# Power.net
KiCad netlist of a schematic drawn in Altium Designer
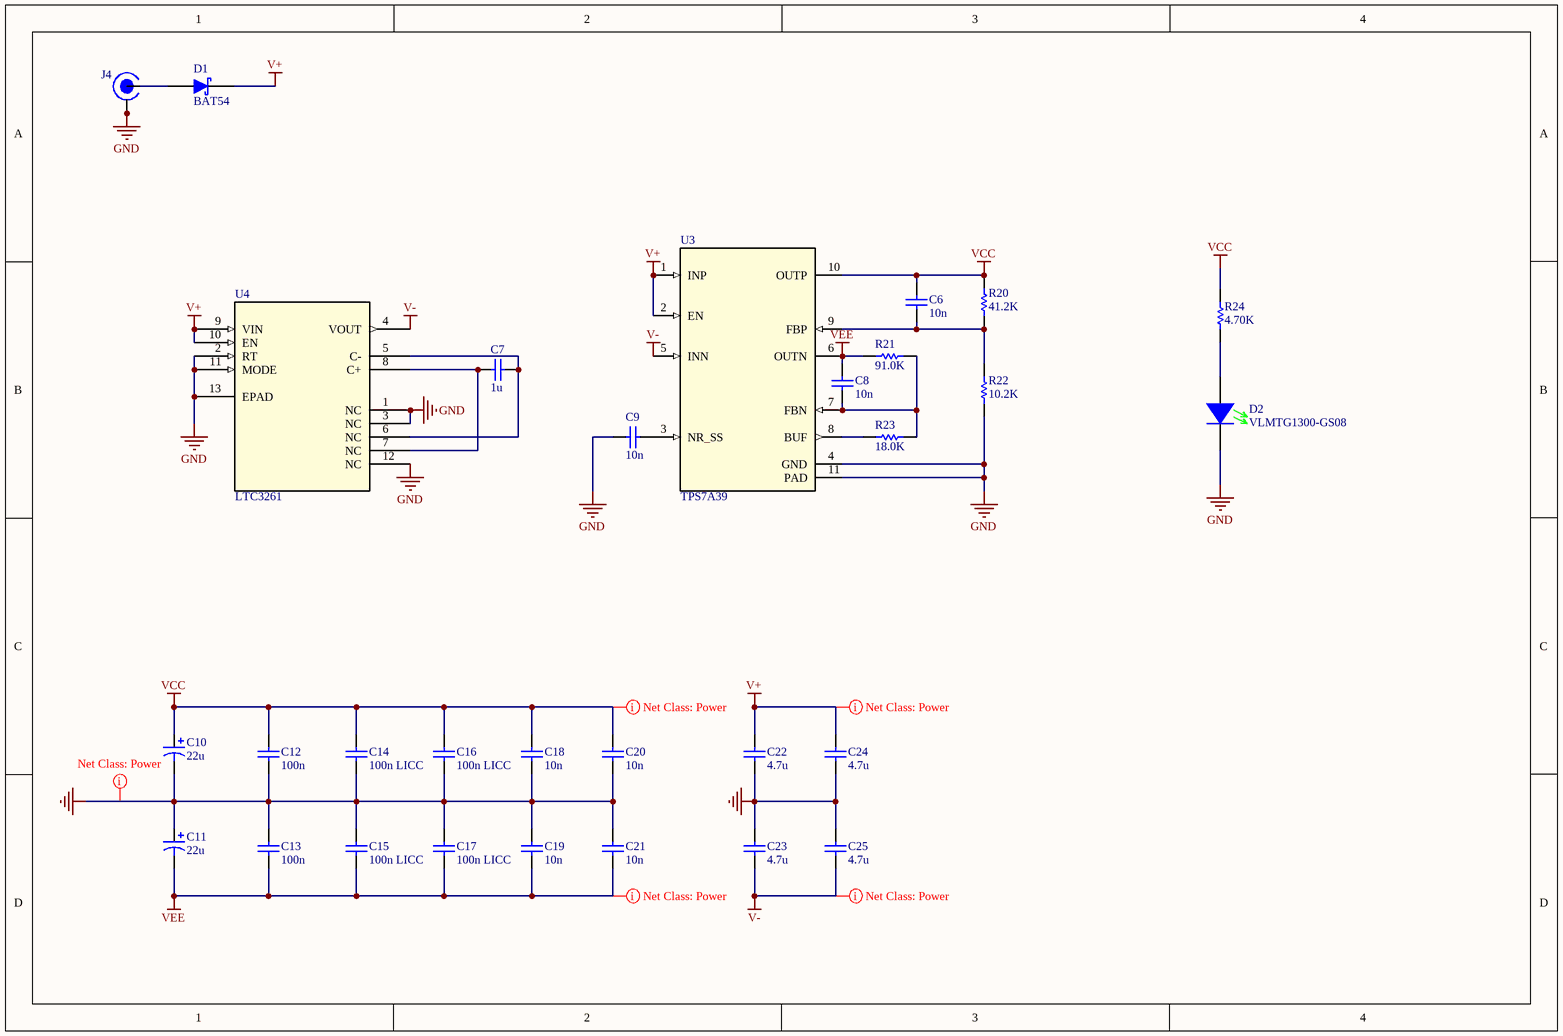
[diagram p0: Power.SchDoc]

(export (version "E")
  (design (tool "Eeschema 10.0.6"))
  (components
    (comp (ref "C6")
      (value "10n")
      (footprint "CAPC0402(1005)50_M")
      (description "CAP CER 10NF±5% 25V C0G 0402")
      (fields
        (field (name "MANUFACTURER") "Murata")
        (field (name "MANUFACTURER PART NUMBER") "GRM1555C1E103JE01D")
      )
      (libsource (lib "Murata GRM 0402") (part "Capacitor_Generic"))
    )
    (comp (ref "C7")
      (value "1u")
      (footprint "CAPC0805(2012)145_M")
      (description "Cap Ceramic 1uF 50V X7R 10% SMD 0805 125C Blister T/R")
      (fields
        (field (name "MANUFACTURER") "Yageo")
        (field (name "MANUFACTURER PART NUMBER") "CC0805KKX7R9BB105")
      )
      (libsource (lib "0805 Caps") (part "CC0805KKX7R9BB105"))
    )
    (comp (ref "C8")
      (value "10n")
      (footprint "CAPC0402(1005)50_M")
      (description "CAP CER 10NF±5% 25V C0G 0402")
      (fields
        (field (name "MANUFACTURER") "Murata")
        (field (name "MANUFACTURER PART NUMBER") "GRM1555C1E103JE01D")
      )
      (libsource (lib "Murata GRM 0402") (part "Capacitor_Generic"))
    )
    (comp (ref "C9")
      (value "10n")
      (footprint "CAPC0402(1005)50_M")
      (description "CAP CER 10NF±5% 25V C0G 0402")
      (fields
        (field (name "MANUFACTURER") "Murata")
        (field (name "MANUFACTURER PART NUMBER") "GRM1555C1E103JE01D")
      )
      (libsource (lib "Murata GRM 0402") (part "Capacitor_Generic"))
    )
    (comp (ref "C10")
      (value "22u")
      (footprint "KEMET B_M")
      (description "CAP TANT 22UF 10% 16V 1411")
      (fields
        (field (name "MANUFACTURER") "KEMET")
        (field (name "MANUFACTURER PART NUMBER") "T491B226K016AT")
      )
      (libsource (lib "Misc Caps") (part "T491B226K016AT"))
    )
    (comp (ref "C11")
      (value "22u")
      (footprint "KEMET B_M")
      (description "CAP TANT 22UF 10% 16V 1411")
      (fields
        (field (name "MANUFACTURER") "KEMET")
        (field (name "MANUFACTURER PART NUMBER") "T491B226K016AT")
      )
      (libsource (lib "Misc Caps") (part "T491B226K016AT"))
    )
    (comp (ref "C12")
      (value "100n")
      (footprint "CAPC0603(1608)100_M")
      (description "CAPACITOR CERAMIC, 0.1UF, 50V, X7R, 10%, 0603")
      (fields
        (field (name "MANUFACTURER") "Yageo")
        (field (name "MANUFACTURER PART NUMBER") "CC0603KRX7R9BB104")
      )
      (libsource (lib "0603 Caps") (part "CC0603KRX7R9BB104"))
    )
    (comp (ref "C13")
      (value "100n")
      (footprint "CAPC0603(1608)100_M")
      (description "CAPACITOR CERAMIC, 0.1UF, 50V, X7R, 10%, 0603")
      (fields
        (field (name "MANUFACTURER") "Yageo")
        (field (name "MANUFACTURER PART NUMBER") "CC0603KRX7R9BB104")
      )
      (libsource (lib "0603 Caps") (part "CC0603KRX7R9BB104"))
    )
    (comp (ref "C14")
      (value "100n LICC")
      (footprint "CAPC0306_M")
      (description "CAP CER 0.1UF 25V X7R 0306")
      (fields
        (field (name "MANUFACTURER") "Taiyo Yuden")
        (field (name "MANUFACTURER PART NUMBER") "TWK107B7104MVHT")
      )
      (libsource (lib "Misc Caps") (part "TWK107B7104MVHT"))
    )
    (comp (ref "C15")
      (value "100n LICC")
      (footprint "CAPC0306_M")
      (description "CAP CER 0.1UF 25V X7R 0306")
      (fields
        (field (name "MANUFACTURER") "Taiyo Yuden")
        (field (name "MANUFACTURER PART NUMBER") "TWK107B7104MVHT")
      )
      (libsource (lib "Misc Caps") (part "TWK107B7104MVHT"))
    )
    (comp (ref "C16")
      (value "100n LICC")
      (footprint "CAPC0306_M")
      (description "CAP CER 0.1UF 25V X7R 0306")
      (fields
        (field (name "MANUFACTURER") "Taiyo Yuden")
        (field (name "MANUFACTURER PART NUMBER") "TWK107B7104MVHT")
      )
      (libsource (lib "Misc Caps") (part "TWK107B7104MVHT"))
    )
    (comp (ref "C17")
      (value "100n LICC")
      (footprint "CAPC0306_M")
      (description "CAP CER 0.1UF 25V X7R 0306")
      (fields
        (field (name "MANUFACTURER") "Taiyo Yuden")
        (field (name "MANUFACTURER PART NUMBER") "TWK107B7104MVHT")
      )
      (libsource (lib "Misc Caps") (part "TWK107B7104MVHT"))
    )
    (comp (ref "C18")
      (value "10n")
      (footprint "CAPC0402(1005)50_M")
      (description "CAP CER 10NF±10% 50V X7R 0402")
      (fields (field (name "PART NUMBER") "GRM155R71H103KA88") (field (name "TOLERANCE") "±10%"))
      (libsource (lib "Murata GRM 0402") (part "Capacitor_Generic"))
    )
    (comp (ref "C19")
      (value "10n")
      (footprint "CAPC0402(1005)50_M")
      (description "CAP CER 10NF±10% 50V X7R 0402")
      (fields (field (name "PART NUMBER") "GRM155R71H103KA88") (field (name "TOLERANCE") "±10%"))
      (libsource (lib "Murata GRM 0402") (part "Capacitor_Generic"))
    )
    (comp (ref "C20")
      (value "10n")
      (footprint "CAPC0402(1005)50_M")
      (description "CAP CER 10NF±10% 50V X7R 0402")
      (fields (field (name "PART NUMBER") "GRM155R71H103KA88") (field (name "TOLERANCE") "±10%"))
      (libsource (lib "Murata GRM 0402") (part "Capacitor_Generic"))
    )
    (comp (ref "C21")
      (value "10n")
      (footprint "CAPC0402(1005)50_M")
      (description "CAP CER 10NF±10% 50V X7R 0402")
      (fields (field (name "PART NUMBER") "GRM155R71H103KA88") (field (name "TOLERANCE") "±10%"))
      (libsource (lib "Murata GRM 0402") (part "Capacitor_Generic"))
    )
    (comp (ref "C22")
      (value "4.7u")
      (footprint "CAPC0805(2012)100_M")
      (description "CAP CER 4.7UF 50V X7R 0805")
      (fields
        (field (name "MANUFACTURER") "Murata")
        (field (name "MANUFACTURER PART NUMBER") "GRM21BZ71H475KE15K")
      )
      (libsource (lib "0805 Caps") (part "GRM21BZ71H475KE15K"))
    )
    (comp (ref "C23")
      (value "4.7u")
      (footprint "CAPC0805(2012)100_M")
      (description "CAP CER 4.7UF 50V X7R 0805")
      (fields
        (field (name "MANUFACTURER") "Murata")
        (field (name "MANUFACTURER PART NUMBER") "GRM21BZ71H475KE15K")
      )
      (libsource (lib "0805 Caps") (part "GRM21BZ71H475KE15K"))
    )
    (comp (ref "C24")
      (value "4.7u")
      (footprint "CAPC0805(2012)100_M")
      (description "CAP CER 4.7UF 50V X7R 0805")
      (fields
        (field (name "MANUFACTURER") "Murata")
        (field (name "MANUFACTURER PART NUMBER") "GRM21BZ71H475KE15K")
      )
      (libsource (lib "0805 Caps") (part "GRM21BZ71H475KE15K"))
    )
    (comp (ref "C25")
      (value "4.7u")
      (footprint "CAPC0805(2012)100_M")
      (description "CAP CER 4.7UF 50V X7R 0805")
      (fields
        (field (name "MANUFACTURER") "Murata")
        (field (name "MANUFACTURER PART NUMBER") "GRM21BZ71H475KE15K")
      )
      (libsource (lib "0805 Caps") (part "GRM21BZ71H475KE15K"))
    )
    (comp (ref "D1")
      (value "BAT54")
      (footprint "INF-PG-SC59_M")
      (description "DIODE SCHOTTKY 30V 200MA TO236AB")
      (fields
        (field (name "MANUFACTURER") "Nexperia USA")
        (field (name "MANUFACTURER PART NUMBER") "BAT54,215")
      )
      (libsource (lib "Discretes") (part "BAT54"))
    )
    (comp (ref "D2")
      (value "VLMTG1300-GS08")
      (footprint "LED0603(1608)_M")
      (description "LED GREEN 0603 SMD")
      (fields (field (name "MANUFACTURER") "Vishay Semiconductors"))
      (libsource (lib "Discretes") (part "VLMTG1300-GS08"))
    )
    (comp (ref "J4")
      (value "2.1/5.5mm")
      (footprint "CUI PJ-002A")
      (description "CONN PWR JACK 2X5.5MM SOLDER")
      (fields (field (name "MANUFACTURER") "CUI") (field (name "MANUFACTURER PART NUMBER") "PJ-002A"))
      (libsource (lib "Connectors") (part "PJ-002A"))
    )
    (comp (ref "R20")
      (value "41.2K")
      (footprint "RESC0402(1005)_M")
      (description "RES 41.2K OHM 1% 1/16W 0402")
      (fields (field (name "PART NUMBER") "RESC0402-41K2-1pct"))
      (libsource (lib "R0402 - 1pct") (part "Resistor_Generic"))
    )
    (comp (ref "R21")
      (value "91.0K")
      (footprint "RESC0402(1005)_M")
      (description "RES 91.0K OHM 1% 1/16W 0402")
      (fields (field (name "PART NUMBER") "RESC0402-91K0-1pct"))
      (libsource (lib "R0402 - 1pct") (part "Resistor_Generic"))
    )
    (comp (ref "R22")
      (value "10.2K")
      (footprint "RESC0402(1005)_M")
      (description "RES 10.2K OHM 1% 1/16W 0402")
      (fields (field (name "PART NUMBER") "RESC0402-10K2-1pct"))
      (libsource (lib "R0402 - 1pct") (part "Resistor_Generic"))
    )
    (comp (ref "R23")
      (value "18.0K")
      (footprint "RESC0402(1005)_M")
      (description "RES 18.0K OHM 1% 1/16W 0402")
      (fields (field (name "PART NUMBER") "RESC0402-18K0-1pct"))
      (libsource (lib "R0402 - 1pct") (part "Resistor_Generic"))
    )
    (comp (ref "R24")
      (value "4.70K")
      (footprint "RESC0603(1608)_M")
      (description "RES 4.70K OHM 1% 1/10W 0603")
      (fields (field (name "PART NUMBER") "RESC0603-4K70-1pct"))
      (libsource (lib "R0603 - 1pct") (part "Resistor_Generic"))
    )
    (comp (ref "U3")
      (value "TPS7A39")
      (footprint "DSC0010J_NV")
      (description "IC REG LINEAR POS/NEG ADJ 10WSON")
      (fields
        (field (name "MANUFACTURER_PART_NUMBER") "TPS7A3901DSCR")
        (field (name "MANUFACTURER") "Texas Instruments")
        (field (name "COPYRIGHT") "Copyright (C) 2022 Ultra Librarian. All rights reserved.")
      )
      (libsource (lib "IC") (part "TPS7A3901DSCR"))
    )
    (comp (ref "U4")
      (value "LTC3261")
      (footprint "MSOP-12_MSE")
      (description "IC REG CHARG PUMP INV 12MSOP")
      (fields
        (field (name "MANUFACTURER_PART_NUMBER") "ltc3261emse#pbf")
        (field (name "MANUFACTURER") "Analog Devices / Linear Technology")
        (field (name "COPYRIGHT") "Copyright (C) 2022 Ultra Librarian. All rights reserved.")
      )
      (libsource (lib "IC") (part "LTC3261EMSE"))
    )
  )
  (nets
    (net (code "1") (name "GND") (class "Default")
      (node (ref "C10") (pin "2") (pinfunction "2_2") (pintype "passive"))
      (node (ref "C11") (pin "1") (pinfunction "1_1") (pintype "passive"))
      (node (ref "C12") (pin "2") (pinfunction "2_2") (pintype "passive"))
      (node (ref "C13") (pin "1") (pinfunction "1_1") (pintype "passive"))
      (node (ref "C14") (pin "2") (pinfunction "2_2") (pintype "passive"))
      (node (ref "C15") (pin "1") (pinfunction "1_1") (pintype "passive"))
      (node (ref "C16") (pin "2") (pinfunction "2_2") (pintype "passive"))
      (node (ref "C17") (pin "1") (pinfunction "1_1") (pintype "passive"))
      (node (ref "C18") (pin "2") (pinfunction "2_2") (pintype "passive"))
      (node (ref "C19") (pin "1") (pinfunction "1_1") (pintype "passive"))
      (node (ref "C20") (pin "2") (pinfunction "2_2") (pintype "passive"))
      (node (ref "C21") (pin "1") (pinfunction "1_1") (pintype "passive"))
      (node (ref "C22") (pin "2") (pinfunction "2_2") (pintype "passive"))
      (node (ref "C23") (pin "1") (pinfunction "1_1") (pintype "passive"))
      (node (ref "C24") (pin "2") (pinfunction "2_2") (pintype "passive"))
      (node (ref "C25") (pin "2") (pinfunction "2_2") (pintype "passive"))
      (node (ref "C9") (pin "2") (pinfunction "2_2") (pintype "passive"))
      (node (ref "D2") (pin "2") (pinfunction "K_2") (pintype "passive"))
      (node (ref "J4") (pin "2") (pinfunction "2_2") (pintype "passive"))
      (node (ref "J4") (pin "3") (pinfunction "3_3") (pintype "passive"))
      (node (ref "R22") (pin "2") (pinfunction "2_2") (pintype "passive"))
      (node (ref "U3") (pin "11") (pinfunction "PAD_11") (pintype "power_in"))
      (node (ref "U3") (pin "4") (pinfunction "GND_4") (pintype "power_in"))
      (node (ref "U4") (pin "1") (pinfunction "NC_1") (pintype "passive"))
      (node (ref "U4") (pin "11") (pinfunction "MODE_11") (pintype "input"))
      (node (ref "U4") (pin "12") (pinfunction "NC_12") (pintype "passive"))
      (node (ref "U4") (pin "13") (pinfunction "EPAD_13") (pintype "passive"))
      (node (ref "U4") (pin "2") (pinfunction "RT_2") (pintype "input"))
      (node (ref "U4") (pin "3") (pinfunction "NC_3") (pintype "passive"))
    )
    (net (code "2") (name "Net-(D1-A)") (class "Default")
      (node (ref "D1") (pin "1") (pinfunction "A_1") (pintype "passive"))
      (node (ref "J4") (pin "1") (pinfunction "1_1") (pintype "passive"))
    )
    (net (code "3") (name "Net-(D2-A)") (class "Default")
      (node (ref "D2") (pin "1") (pinfunction "A_1") (pintype "passive"))
      (node (ref "R24") (pin "2") (pinfunction "2_2") (pintype "passive"))
    )
    (net (code "4") (name "Net-(U3-BUF)") (class "Default")
      (node (ref "R23") (pin "2") (pinfunction "2_2") (pintype "passive"))
      (node (ref "U3") (pin "8") (pinfunction "BUF_8") (pintype "output"))
    )
    (net (code "5") (name "Net-(U3-FBN)") (class "Default")
      (node (ref "C8") (pin "1") (pinfunction "1_1") (pintype "passive"))
      (node (ref "R21") (pin "1") (pinfunction "1_1") (pintype "passive"))
      (node (ref "R23") (pin "1") (pinfunction "1_1") (pintype "passive"))
      (node (ref "U3") (pin "7") (pinfunction "FBN_7") (pintype "input"))
    )
    (net (code "6") (name "Net-(U3-FBP)") (class "Default")
      (node (ref "C6") (pin "1") (pinfunction "1_1") (pintype "passive"))
      (node (ref "R20") (pin "2") (pinfunction "2_2") (pintype "passive"))
      (node (ref "R22") (pin "1") (pinfunction "1_1") (pintype "passive"))
      (node (ref "U3") (pin "9") (pinfunction "FBP_9") (pintype "input"))
    )
    (net (code "7") (name "Net-(U3-NR_SS)") (class "Default")
      (node (ref "C9") (pin "1") (pinfunction "1_1") (pintype "passive"))
      (node (ref "U3") (pin "3") (pinfunction "NR_SS_3") (pintype "input"))
    )
    (net (code "8") (name "Net-(U4-C+)") (class "Default")
      (node (ref "C7") (pin "1") (pinfunction "1_1") (pintype "passive"))
      (node (ref "U4") (pin "7") (pinfunction "NC_7") (pintype "passive"))
      (node (ref "U4") (pin "8") (pinfunction "C+_8") (pintype "passive"))
    )
    (net (code "9") (name "Net-(U4-C-)") (class "Default")
      (node (ref "C7") (pin "2") (pinfunction "2_2") (pintype "passive"))
      (node (ref "U4") (pin "5") (pinfunction "C-_5") (pintype "passive"))
      (node (ref "U4") (pin "6") (pinfunction "NC_6") (pintype "passive"))
    )
    (net (code "10") (name "V+") (class "Default")
      (node (ref "C22") (pin "1") (pinfunction "1_1") (pintype "passive"))
      (node (ref "C24") (pin "1") (pinfunction "1_1") (pintype "passive"))
      (node (ref "D1") (pin "3") (pinfunction "K_3") (pintype "passive"))
      (node (ref "U3") (pin "1") (pinfunction "INP_1") (pintype "input"))
      (node (ref "U3") (pin "2") (pinfunction "EN_2") (pintype "input"))
      (node (ref "U4") (pin "10") (pinfunction "EN_10") (pintype "input"))
      (node (ref "U4") (pin "9") (pinfunction "VIN_9") (pintype "input"))
    )
    (net (code "11") (name "V-") (class "Default")
      (node (ref "C23") (pin "2") (pinfunction "2_2") (pintype "passive"))
      (node (ref "C25") (pin "1") (pinfunction "1_1") (pintype "passive"))
      (node (ref "U3") (pin "5") (pinfunction "INN_5") (pintype "input"))
      (node (ref "U4") (pin "4") (pinfunction "VOUT_4") (pintype "output"))
    )
    (net (code "12") (name "VCC") (class "Default")
      (node (ref "C10") (pin "1") (pinfunction "1_1") (pintype "passive"))
      (node (ref "C12") (pin "1") (pinfunction "1_1") (pintype "passive"))
      (node (ref "C14") (pin "1") (pinfunction "1_1") (pintype "passive"))
      (node (ref "C16") (pin "1") (pinfunction "1_1") (pintype "passive"))
      (node (ref "C18") (pin "1") (pinfunction "1_1") (pintype "passive"))
      (node (ref "C20") (pin "1") (pinfunction "1_1") (pintype "passive"))
      (node (ref "C6") (pin "2") (pinfunction "2_2") (pintype "passive"))
      (node (ref "R20") (pin "1") (pinfunction "1_1") (pintype "passive"))
      (node (ref "R24") (pin "1") (pinfunction "1_1") (pintype "passive"))
      (node (ref "U3") (pin "10") (pinfunction "OUTP_10") (pintype "power_in"))
    )
    (net (code "13") (name "VEE") (class "Default")
      (node (ref "C11") (pin "2") (pinfunction "2_2") (pintype "passive"))
      (node (ref "C13") (pin "2") (pinfunction "2_2") (pintype "passive"))
      (node (ref "C15") (pin "2") (pinfunction "2_2") (pintype "passive"))
      (node (ref "C17") (pin "2") (pinfunction "2_2") (pintype "passive"))
      (node (ref "C19") (pin "2") (pinfunction "2_2") (pintype "passive"))
      (node (ref "C21") (pin "2") (pinfunction "2_2") (pintype "passive"))
      (node (ref "C8") (pin "2") (pinfunction "2_2") (pintype "passive"))
      (node (ref "R21") (pin "2") (pinfunction "2_2") (pintype "passive"))
      (node (ref "U3") (pin "6") (pinfunction "OUTN_6") (pintype "power_in"))
    )
  )
)
